# shift_board.net
KiCad netlist of a schematic drawn in Altium Designer
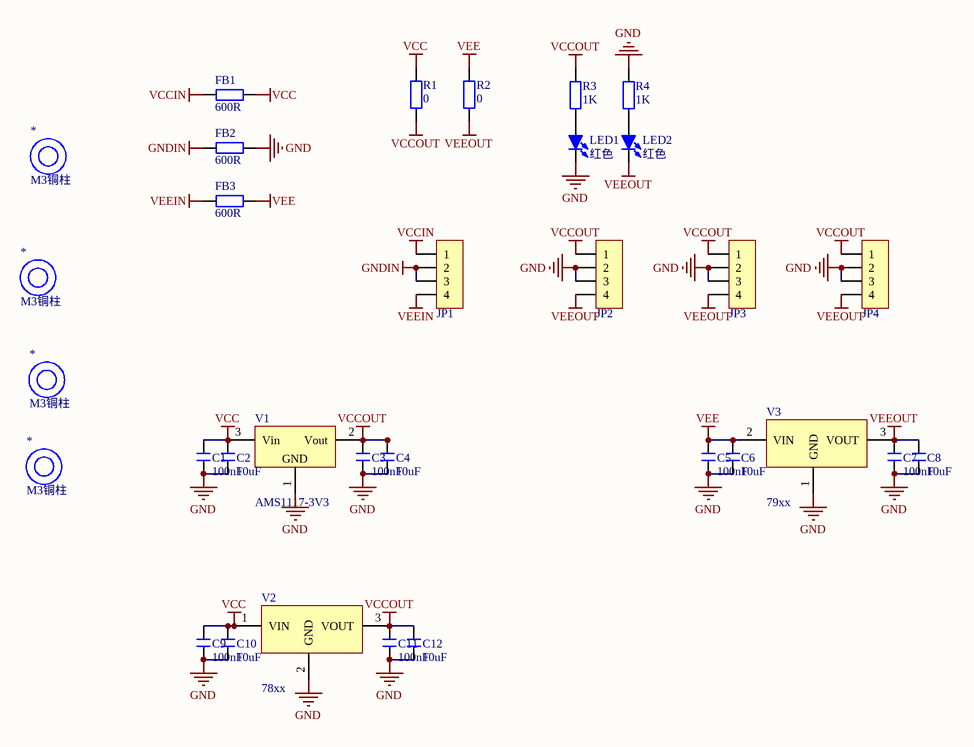
[diagram p0: shift board.SchDoc]

(export (version "E")
  (design (tool "Eeschema 10.0.6"))
  (components
    (comp (ref "C1")
      (value "100nF")
      (footprint "C 0603_L")
      (description "无极性贴片电容")
      (fields (field (name "版权归属") "源创客"))
      (libsource (lib "IL") (part "C"))
    )
    (comp (ref "C2")
      (value "10uF")
      (footprint "C 0603_L")
      (description "无极性贴片电容")
      (fields (field (name "版权归属") "源创客"))
      (libsource (lib "IL") (part "C"))
    )
    (comp (ref "C3")
      (value "100nF")
      (footprint "C 0603_L")
      (description "无极性贴片电容")
      (fields (field (name "版权归属") "源创客"))
      (libsource (lib "IL") (part "C"))
    )
    (comp (ref "C4")
      (value "10uF")
      (footprint "C 0603_L")
      (description "无极性贴片电容")
      (fields (field (name "版权归属") "源创客"))
      (libsource (lib "IL") (part "C"))
    )
    (comp (ref "C5")
      (value "100nF")
      (footprint "C 0603_L")
      (description "无极性贴片电容")
      (fields (field (name "版权归属") "源创客"))
      (libsource (lib "IL") (part "C"))
    )
    (comp (ref "C6")
      (value "10uF")
      (footprint "C 0603_L")
      (description "无极性贴片电容")
      (fields (field (name "版权归属") "源创客"))
      (libsource (lib "IL") (part "C"))
    )
    (comp (ref "C7")
      (value "100nF")
      (footprint "C 0603_L")
      (description "无极性贴片电容")
      (fields (field (name "版权归属") "源创客"))
      (libsource (lib "IL") (part "C"))
    )
    (comp (ref "C8")
      (value "10uF")
      (footprint "C 0603_L")
      (description "无极性贴片电容")
      (fields (field (name "版权归属") "源创客"))
      (libsource (lib "IL") (part "C"))
    )
    (comp (ref "C9")
      (value "100nF")
      (footprint "C 0603_L")
      (description "无极性贴片电容")
      (fields (field (name "版权归属") "源创客"))
      (libsource (lib "IL") (part "C"))
    )
    (comp (ref "C10")
      (value "10uF")
      (footprint "C 0603_L")
      (description "无极性贴片电容")
      (fields (field (name "版权归属") "源创客"))
      (libsource (lib "IL") (part "C"))
    )
    (comp (ref "C11")
      (value "100nF")
      (footprint "C 0603_L")
      (description "无极性贴片电容")
      (fields (field (name "版权归属") "源创客"))
      (libsource (lib "IL") (part "C"))
    )
    (comp (ref "C12")
      (value "10uF")
      (footprint "C 0603_L")
      (description "无极性贴片电容")
      (fields (field (name "版权归属") "源创客"))
      (libsource (lib "IL") (part "C"))
    )
    (comp (ref "FB1") (value "600R") (footprint "FB-0805") (libsource (lib "Library") (part "FB")))
    (comp (ref "FB2") (value "600R") (footprint "FB-0805") (libsource (lib "Library") (part "FB")))
    (comp (ref "FB3") (value "600R") (footprint "FB-0805") (libsource (lib "Library") (part "FB")))
    (comp (ref "JP1")
      (value "HDR-1X4")
      (footprint "VH3.96-LI-4P")
      (description "4P接插件")
      (fields (field (name "版权归属") "源创客"))
      (libsource (lib "IL") (part "Header 4_1"))
    )
    (comp (ref "JP2")
      (value "HDR-1X4")
      (footprint "VH3.96-LI-4P")
      (description "4P接插件")
      (fields (field (name "版权归属") "源创客"))
      (libsource (lib "IL") (part "Header 4_1"))
    )
    (comp (ref "JP3")
      (value "HDR-1X4")
      (footprint "VH3.96-LI-4P")
      (description "4P接插件")
      (fields (field (name "版权归属") "源创客"))
      (libsource (lib "IL") (part "Header 4_1"))
    )
    (comp (ref "JP4")
      (value "HDR-1X4")
      (footprint "VH3.96-LI-4P")
      (description "4P接插件")
      (fields (field (name "版权归属") "源创客"))
      (libsource (lib "IL") (part "Header 4_1"))
    )
    (comp (ref "LED1")
      (value "红色")
      (footprint "LED 0805G")
      (description "贴片LED")
      (fields (field (name "版权归属") "源创客"))
      (libsource (lib "IL") (part "LED-SMD"))
    )
    (comp (ref "LED2")
      (value "红色")
      (footprint "LED 0805G")
      (description "贴片LED")
      (fields (field (name "版权归属") "源创客"))
      (libsource (lib "IL") (part "LED-SMD"))
    )
    (comp (ref "R1")
      (value "0")
      (footprint "R 0603_L")
      (description "贴片电阻")
      (fields (field (name "版权归属") "源创客"))
      (libsource (lib "IL") (part "R"))
    )
    (comp (ref "R2")
      (value "0")
      (footprint "R 0603_L")
      (description "贴片电阻")
      (fields (field (name "版权归属") "源创客"))
      (libsource (lib "IL") (part "R"))
    )
    (comp (ref "R3")
      (value "1K")
      (footprint "R 0603_L")
      (description "贴片电阻")
      (fields (field (name "版权归属") "源创客"))
      (libsource (lib "IL") (part "R"))
    )
    (comp (ref "R4")
      (value "1K")
      (footprint "R 0603_L")
      (description "贴片电阻")
      (fields (field (name "版权归属") "源创客"))
      (libsource (lib "IL") (part "R"))
    )
    (comp (ref "V1")
      (value "AMS1117-3V3")
      (footprint "SOT223_L")
      (description "三端稳压芯片")
      (fields (field (name "版权归属") "源创客"))
      (libsource (lib "IL") (part "AMS1117"))
    )
    (comp (ref "V2")
      (value "78xx")
      (footprint "TO252")
      (description "线性稳压芯片")
      (fields (field (name "版权归属") "源创客"))
      (libsource (lib "IL") (part "78xx"))
    )
    (comp (ref "V3")
      (value "79xx")
      (footprint "TO252")
      (description "线性稳压芯片")
      (fields (field (name "版权归属") "源创客"))
      (libsource (lib "IL") (part "79xx"))
    )
  )
  (nets
    (net (code "1") (name "GND") (class "Default")
      (node (ref "C1") (pin "1") (pinfunction "1_1") (pintype "passive"))
      (node (ref "C10") (pin "1") (pinfunction "1_1") (pintype "passive"))
      (node (ref "C11") (pin "1") (pinfunction "1_1") (pintype "passive"))
      (node (ref "C12") (pin "1") (pinfunction "1_1") (pintype "passive"))
      (node (ref "C2") (pin "1") (pinfunction "1_1") (pintype "passive"))
      (node (ref "C3") (pin "1") (pinfunction "1_1") (pintype "passive"))
      (node (ref "C4") (pin "1") (pinfunction "1_1") (pintype "passive"))
      (node (ref "C5") (pin "1") (pinfunction "1_1") (pintype "passive"))
      (node (ref "C6") (pin "1") (pinfunction "1_1") (pintype "passive"))
      (node (ref "C7") (pin "1") (pinfunction "1_1") (pintype "passive"))
      (node (ref "C8") (pin "1") (pinfunction "1_1") (pintype "passive"))
      (node (ref "C9") (pin "1") (pinfunction "1_1") (pintype "passive"))
      (node (ref "FB2") (pin "2") (pinfunction "2_2") (pintype "passive"))
      (node (ref "JP2") (pin "2") (pinfunction "2_2") (pintype "passive"))
      (node (ref "JP2") (pin "3") (pinfunction "3_3") (pintype "passive"))
      (node (ref "JP3") (pin "2") (pinfunction "2_2") (pintype "passive"))
      (node (ref "JP3") (pin "3") (pinfunction "3_3") (pintype "passive"))
      (node (ref "JP4") (pin "2") (pinfunction "2_2") (pintype "passive"))
      (node (ref "JP4") (pin "3") (pinfunction "3_3") (pintype "passive"))
      (node (ref "LED1") (pin "2") (pinfunction "K_2") (pintype "passive"))
      (node (ref "R4") (pin "2") (pinfunction "2_2") (pintype "passive"))
      (node (ref "V1") (pin "1") (pinfunction "GND_1") (pintype "passive"))
      (node (ref "V2") (pin "2") (pinfunction "GND_2") (pintype "passive"))
      (node (ref "V3") (pin "1") (pinfunction "GND_1") (pintype "passive"))
    )
    (net (code "2") (name "GNDIN") (class "Default")
      (node (ref "FB2") (pin "1") (pinfunction "1_1") (pintype "passive"))
      (node (ref "JP1") (pin "2") (pinfunction "2_2") (pintype "passive"))
      (node (ref "JP1") (pin "3") (pinfunction "3_3") (pintype "passive"))
    )
    (net (code "3") (name "Net-(LED1-A)") (class "Default")
      (node (ref "LED1") (pin "1") (pinfunction "A_1") (pintype "passive"))
      (node (ref "R3") (pin "1") (pinfunction "1_1") (pintype "passive"))
    )
    (net (code "4") (name "Net-(LED2-A)") (class "Default")
      (node (ref "LED2") (pin "1") (pinfunction "A_1") (pintype "passive"))
      (node (ref "R4") (pin "1") (pinfunction "1_1") (pintype "passive"))
    )
    (net (code "5") (name "VCC") (class "Default")
      (node (ref "C1") (pin "2") (pinfunction "2_2") (pintype "passive"))
      (node (ref "C10") (pin "2") (pinfunction "2_2") (pintype "passive"))
      (node (ref "C2") (pin "2") (pinfunction "2_2") (pintype "passive"))
      (node (ref "C9") (pin "2") (pinfunction "2_2") (pintype "passive"))
      (node (ref "FB1") (pin "2") (pinfunction "2_2") (pintype "passive"))
      (node (ref "R1") (pin "2") (pinfunction "2_2") (pintype "passive"))
      (node (ref "V1") (pin "3") (pinfunction "Vin_3") (pintype "passive"))
      (node (ref "V2") (pin "1") (pinfunction "VIN_1") (pintype "passive"))
    )
    (net (code "6") (name "VCCIN") (class "Default")
      (node (ref "FB1") (pin "1") (pinfunction "1_1") (pintype "passive"))
      (node (ref "JP1") (pin "1") (pinfunction "1_1") (pintype "passive"))
    )
    (net (code "7") (name "VCCOUT") (class "Default")
      (node (ref "C11") (pin "2") (pinfunction "2_2") (pintype "passive"))
      (node (ref "C12") (pin "2") (pinfunction "2_2") (pintype "passive"))
      (node (ref "C3") (pin "2") (pinfunction "2_2") (pintype "passive"))
      (node (ref "C4") (pin "2") (pinfunction "2_2") (pintype "passive"))
      (node (ref "JP2") (pin "1") (pinfunction "1_1") (pintype "passive"))
      (node (ref "JP3") (pin "1") (pinfunction "1_1") (pintype "passive"))
      (node (ref "JP4") (pin "1") (pinfunction "1_1") (pintype "passive"))
      (node (ref "R1") (pin "1") (pinfunction "1_1") (pintype "passive"))
      (node (ref "R3") (pin "2") (pinfunction "2_2") (pintype "passive"))
      (node (ref "V1") (pin "2") (pinfunction "Vout_2") (pintype "passive"))
      (node (ref "V2") (pin "3") (pinfunction "VOUT_3") (pintype "passive"))
    )
    (net (code "8") (name "VEE") (class "Default")
      (node (ref "C5") (pin "2") (pinfunction "2_2") (pintype "passive"))
      (node (ref "C6") (pin "2") (pinfunction "2_2") (pintype "passive"))
      (node (ref "FB3") (pin "2") (pinfunction "2_2") (pintype "passive"))
      (node (ref "R2") (pin "2") (pinfunction "2_2") (pintype "passive"))
      (node (ref "V3") (pin "2") (pinfunction "VIN_2") (pintype "passive"))
    )
    (net (code "9") (name "VEEIN") (class "Default")
      (node (ref "FB3") (pin "1") (pinfunction "1_1") (pintype "passive"))
      (node (ref "JP1") (pin "4") (pinfunction "4_4") (pintype "passive"))
    )
    (net (code "10") (name "VEEOUT") (class "Default")
      (node (ref "C7") (pin "2") (pinfunction "2_2") (pintype "passive"))
      (node (ref "C8") (pin "2") (pinfunction "2_2") (pintype "passive"))
      (node (ref "JP2") (pin "4") (pinfunction "4_4") (pintype "passive"))
      (node (ref "JP3") (pin "4") (pinfunction "4_4") (pintype "passive"))
      (node (ref "JP4") (pin "4") (pinfunction "4_4") (pintype "passive"))
      (node (ref "LED2") (pin "2") (pinfunction "K_2") (pintype "passive"))
      (node (ref "R2") (pin "1") (pinfunction "1_1") (pintype "passive"))
      (node (ref "V3") (pin "3") (pinfunction "VOUT_3") (pintype "passive"))
    )
  )
)
